# TPMP1470GJ-Z.net
KiCad netlist of a schematic drawn in Altium Designer
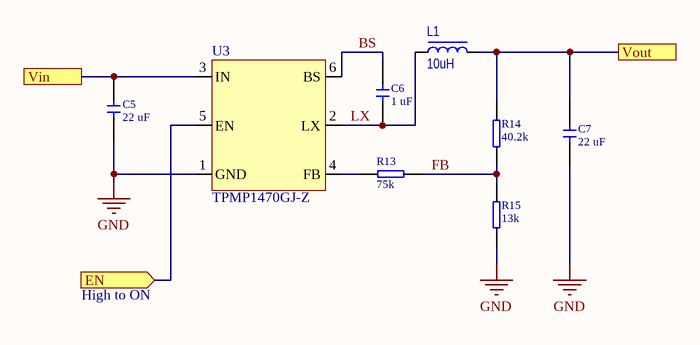
[diagram p0: TPMP1470GJ-Z.SchDoc]

(export (version "E")
  (design (tool "Eeschema 10.0.6"))
  (components
    (comp (ref "C5")
      (value "22 uF")
      (footprint "CERCAP 0805")
      (description "Capacitor")
      (fields (field (name "Comment") "CERCAP 0805 22 uF * X7R"))
      (libsource (lib "!main") (part "!Capacitor"))
    )
    (comp (ref "C6")
      (value "1 uF")
      (footprint "CERCAP 0603")
      (description "Capacitor")
      (fields (field (name "Comment") "CERCAP 0603 1 uF * X7R"))
      (libsource (lib "!main") (part "!Capacitor"))
    )
    (comp (ref "C7")
      (value "22 uF")
      (footprint "CERCAP 0805")
      (description "Capacitor")
      (fields (field (name "Comment") "CERCAP 0805 22 uF * X7R"))
      (libsource (lib "!main") (part "!Capacitor"))
    )
    (comp (ref "L1")
      (value "10uH")
      (footprint "FXL0420")
      (description "Inductor")
      (fields (field (name "Comment") "FXL0420 10uH"))
      (libsource (lib "!main") (part "Inductor"))
    )
    (comp (ref "R13")
      (value "75k")
      (footprint "RES 0402")
      (description "Resistor")
      (fields (field (name "Comment") "RES 0402 75k"))
      (libsource (lib "!main") (part "!Resistor"))
    )
    (comp (ref "R14")
      (value "40.2k")
      (footprint "RES 0402")
      (description "Resistor")
      (fields (field (name "Comment") "RES 0402 40.2k"))
      (libsource (lib "!main") (part "!Resistor"))
    )
    (comp (ref "R15")
      (value "13k")
      (footprint "RES 0402")
      (description "Resistor")
      (fields (field (name "Comment") "RES 0402 13k"))
      (libsource (lib "!main") (part "!Resistor"))
    )
    (comp (ref "U3")
      (value "TPMP1470GJ-Z")
      (footprint "SOT23-6")
      (libsource (lib "my_sch_lib") (part "TPMP1470GJ-Z"))
    )
  )
  (nets
    (net (code "1") (name "/BS") (class "Default")
      (node (ref "C6") (pin "2") (pintype "passive"))
      (node (ref "U3") (pin "6") (pinfunction "BS_6") (pintype "passive"))
    )
    (net (code "2") (name "/EN") (class "Default")
      (node (ref "U3") (pin "5") (pinfunction "EN_5") (pintype "passive"))
    )
    (net (code "3") (name "/FB") (class "Default")
      (node (ref "R13") (pin "2") (pinfunction "12_2") (pintype "passive"))
      (node (ref "R14") (pin "1") (pinfunction "11_1") (pintype "passive"))
      (node (ref "R15") (pin "2") (pinfunction "12_2") (pintype "passive"))
    )
    (net (code "4") (name "/LX") (class "Default")
      (node (ref "C6") (pin "1") (pintype "passive"))
      (node (ref "L1") (pin "1") (pinfunction "7_1") (pintype "passive"))
      (node (ref "U3") (pin "2") (pinfunction "LX_2") (pintype "passive"))
    )
    (net (code "5") (name "/Vin") (class "Default")
      (node (ref "C5") (pin "2") (pintype "passive"))
      (node (ref "U3") (pin "3") (pinfunction "IN_3") (pintype "passive"))
    )
    (net (code "6") (name "/Vout") (class "Default")
      (node (ref "C7") (pin "2") (pintype "passive"))
      (node (ref "L1") (pin "2") (pinfunction "8_2") (pintype "passive"))
      (node (ref "R14") (pin "2") (pinfunction "12_2") (pintype "passive"))
    )
    (net (code "7") (name "GND") (class "Default")
      (node (ref "C5") (pin "1") (pintype "passive"))
      (node (ref "C7") (pin "1") (pintype "passive"))
      (node (ref "R15") (pin "1") (pinfunction "11_1") (pintype "passive"))
      (node (ref "U3") (pin "1") (pinfunction "GND_1") (pintype "passive"))
    )
    (net (code "8") (name "Net-(R13-11)") (class "Default")
      (node (ref "R13") (pin "1") (pinfunction "11_1") (pintype "passive"))
      (node (ref "U3") (pin "4") (pinfunction "FB_4") (pintype "passive"))
    )
  )
)
